# WL_PGA_ATT.net
KiCad netlist of a schematic drawn in Altium Designer
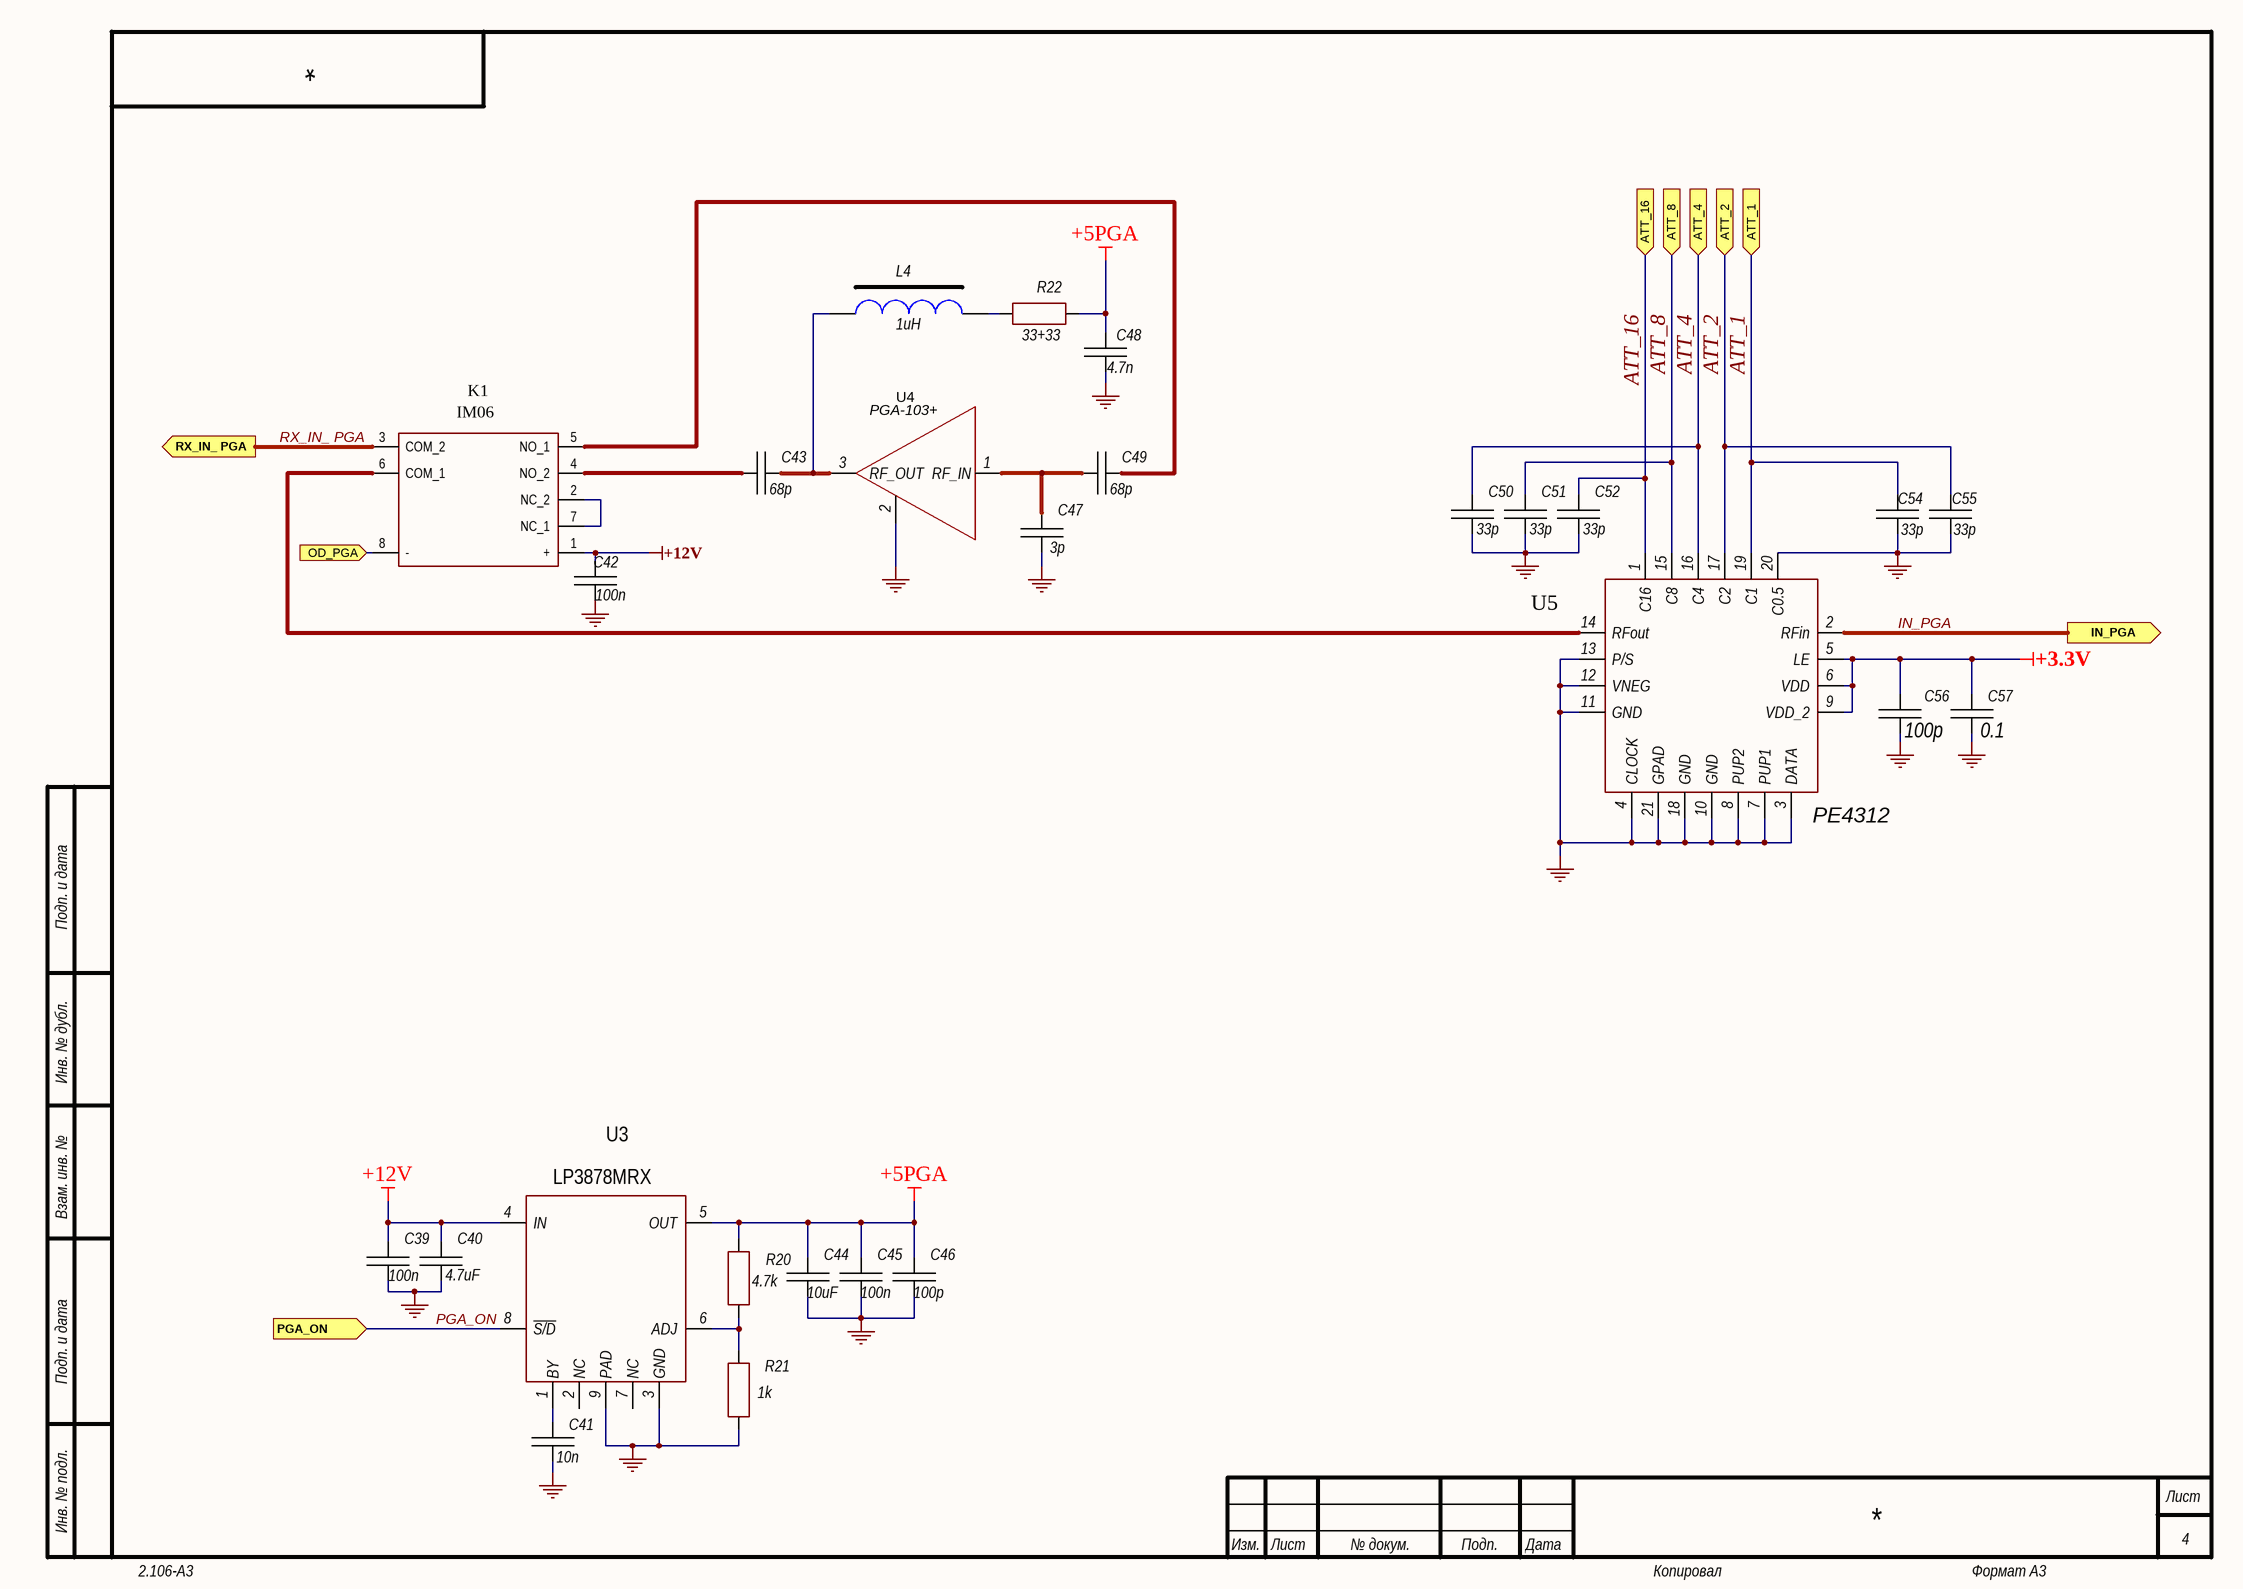
[diagram p0: WL_PGA_ATT.SchDoc]

(export (version "E")
  (design (tool "Eeschema 10.0.6"))
  (components
    (comp (ref "C39")
      (value "100n")
      (footprint "standard:CH0805C")
      (libsource (lib "Discrete") (part "Capacitor"))
    )
    (comp (ref "C40")
      (value "4.7uF")
      (footprint "standard:CH0805C")
      (libsource (lib "Discrete") (part "Capacitor"))
    )
    (comp (ref "C41")
      (value "10n")
      (footprint "standard:CH0805C")
      (libsource (lib "Discrete") (part "Capacitor"))
    )
    (comp (ref "C42")
      (value "100n")
      (footprint "standard:CH0805C")
      (libsource (lib "Discrete") (part "Capacitor"))
    )
    (comp (ref "C43")
      (value "68p")
      (footprint "standard:CH0805C")
      (libsource (lib "Discrete") (part "Capacitor"))
    )
    (comp (ref "C44")
      (value "10uF")
      (footprint "standard:CH0805C")
      (libsource (lib "Discrete") (part "Capacitor"))
    )
    (comp (ref "C45")
      (value "100n")
      (footprint "standard:CH0805C")
      (libsource (lib "Discrete") (part "Capacitor"))
    )
    (comp (ref "C46")
      (value "100p")
      (footprint "standard:CH0805C")
      (libsource (lib "Discrete") (part "Capacitor"))
    )
    (comp (ref "C47")
      (value "3p")
      (footprint "standard:CH0805C")
      (libsource (lib "Discrete") (part "Capacitor"))
    )
    (comp (ref "C48")
      (value "4.7n")
      (footprint "standard:CH0805C")
      (libsource (lib "Discrete") (part "Capacitor"))
    )
    (comp (ref "C49")
      (value "68p")
      (footprint "standard:CH0805C")
      (libsource (lib "Discrete") (part "Capacitor"))
    )
    (comp (ref "C50")
      (value "33p")
      (footprint "standard:CH0603C")
      (libsource (lib "Discrete") (part "Capacitor"))
    )
    (comp (ref "C51")
      (value "33p")
      (footprint "standard:CH0603C")
      (libsource (lib "Discrete") (part "Capacitor"))
    )
    (comp (ref "C52")
      (value "33p")
      (footprint "standard:CH0603C")
      (libsource (lib "Discrete") (part "Capacitor"))
    )
    (comp (ref "C54")
      (value "33p")
      (footprint "standard:CH0603C")
      (libsource (lib "Discrete") (part "Capacitor"))
    )
    (comp (ref "C55")
      (value "33p")
      (footprint "standard:CH0603C")
      (libsource (lib "Discrete") (part "Capacitor"))
    )
    (comp (ref "C56")
      (value "100p")
      (footprint "standard:CH0805C")
      (libsource (lib "Discrete") (part "Capacitor"))
    )
    (comp (ref "C57")
      (value "0.1")
      (footprint "standard:CH0805C")
      (libsource (lib "Discrete") (part "Capacitor"))
    )
    (comp (ref "K1") (value "IM06") (footprint "IM06") (libsource (lib "Relay") (part "IM06-V1")))
    (comp (ref "L4") (value "1uH") (footprint "L1210") (libsource (lib "Transformers") (part "TRANS")))
    (comp (ref "R20")
      (value "4.7k")
      (footprint "standard:CH0805R")
      (libsource (lib "Discrete") (part "Resistor"))
    )
    (comp (ref "R21")
      (value "1k")
      (footprint "standard:CH0805R")
      (libsource (lib "Discrete") (part "Resistor"))
    )
    (comp (ref "R22") (value "33+33") (footprint "WL_RFFC:CH1206R") (libsource (lib "") (part "Resistor_1")))
    (comp (ref "U3")
      (value "LP3878MRX")
      (footprint "8-SOIC (PAD)")
      (libsource (lib "Power Supplies") (part "LP3878"))
    )
    (comp (ref "U4") (value "PGA-103+") (footprint "SOT89_123") (libsource (lib "Digital") (part "PGA-103+")))
    (comp (ref "U5") (value "PE4312") (footprint "20-QFN (4x4)") (libsource (lib "Digital") (part "PE4302")))
  )
  (nets
    (net (code "1") (name "+3.3V") (class "Default")
      (node (ref "C56") (pin "1") (pinfunction "1_1") (pintype "passive"))
      (node (ref "C57") (pin "1") (pinfunction "1_1") (pintype "passive"))
      (node (ref "U5") (pin "5") (pinfunction "LE_5") (pintype "passive"))
      (node (ref "U5") (pin "6") (pinfunction "VDD_6") (pintype "passive"))
      (node (ref "U5") (pin "9") (pinfunction "VDD_2_9") (pintype "passive"))
    )
    (net (code "2") (name "+5PGA") (class "Default")
      (node (ref "C44") (pin "2") (pinfunction "2_2") (pintype "passive"))
      (node (ref "C45") (pin "2") (pinfunction "2_2") (pintype "passive"))
      (node (ref "C46") (pin "2") (pinfunction "2_2") (pintype "passive"))
      (node (ref "C48") (pin "2") (pinfunction "2_2") (pintype "passive"))
      (node (ref "R20") (pin "2") (pinfunction "2_2") (pintype "passive"))
      (node (ref "R22") (pin "2") (pinfunction "2_2") (pintype "passive"))
      (node (ref "U3") (pin "5") (pinfunction "OUT_5") (pintype "power_in"))
    )
    (net (code "3") (name "+12V") (class "Default")
      (node (ref "C39") (pin "2") (pinfunction "2_2") (pintype "passive"))
      (node (ref "C40") (pin "2") (pinfunction "2_2") (pintype "passive"))
      (node (ref "C42") (pin "2") (pinfunction "2_2") (pintype "passive"))
      (node (ref "K1") (pin "1") (pinfunction "+_1") (pintype "passive"))
      (node (ref "U3") (pin "4") (pinfunction "IN_4") (pintype "power_in"))
    )
    (net (code "4") (name "/ATT_1") (class "Default")
      (node (ref "C54") (pin "2") (pinfunction "2_2") (pintype "passive"))
      (node (ref "U5") (pin "19") (pinfunction "C1_19") (pintype "passive"))
    )
    (net (code "5") (name "/ATT_2") (class "Default")
      (node (ref "C55") (pin "2") (pinfunction "2_2") (pintype "passive"))
      (node (ref "U5") (pin "17") (pinfunction "C2_17") (pintype "passive"))
    )
    (net (code "6") (name "/ATT_4") (class "Default")
      (node (ref "C50") (pin "2") (pinfunction "2_2") (pintype "passive"))
      (node (ref "U5") (pin "16") (pinfunction "C4_16") (pintype "passive"))
    )
    (net (code "7") (name "/ATT_8") (class "Default")
      (node (ref "C51") (pin "2") (pinfunction "2_2") (pintype "passive"))
      (node (ref "U5") (pin "15") (pinfunction "C8_15") (pintype "passive"))
    )
    (net (code "8") (name "/ATT_16") (class "Default")
      (node (ref "C52") (pin "2") (pinfunction "2_2") (pintype "passive"))
      (node (ref "U5") (pin "1") (pinfunction "C16_1") (pintype "passive"))
    )
    (net (code "9") (name "/IN_PGA") (class "Default")
      (node (ref "U5") (pin "2") (pinfunction "RFin_2") (pintype "passive"))
    )
    (net (code "10") (name "/OD_PGA") (class "Default")
      (node (ref "K1") (pin "8") (pinfunction "-_8") (pintype "passive"))
    )
    (net (code "11") (name "/PGA_ON") (class "Default")
      (node (ref "U3") (pin "8") (pinfunction "~{S/D}_8") (pintype "power_in"))
    )
    (net (code "12") (name "/RX_IN_ PGA") (class "Default")
      (node (ref "K1") (pin "3") (pinfunction "COM_2_3") (pintype "passive"))
    )
    (net (code "13") (name "GND") (class "Default")
      (node (ref "C39") (pin "1") (pinfunction "1_1") (pintype "passive"))
      (node (ref "C40") (pin "1") (pinfunction "1_1") (pintype "passive"))
      (node (ref "C41") (pin "1") (pinfunction "1_1") (pintype "passive"))
      (node (ref "C42") (pin "1") (pinfunction "1_1") (pintype "passive"))
      (node (ref "C44") (pin "1") (pinfunction "1_1") (pintype "passive"))
      (node (ref "C45") (pin "1") (pinfunction "1_1") (pintype "passive"))
      (node (ref "C46") (pin "1") (pinfunction "1_1") (pintype "passive"))
      (node (ref "C47") (pin "1") (pinfunction "1_1") (pintype "passive"))
      (node (ref "C48") (pin "1") (pinfunction "1_1") (pintype "passive"))
      (node (ref "C50") (pin "1") (pinfunction "1_1") (pintype "passive"))
      (node (ref "C51") (pin "1") (pinfunction "1_1") (pintype "passive"))
      (node (ref "C52") (pin "1") (pinfunction "1_1") (pintype "passive"))
      (node (ref "C54") (pin "1") (pinfunction "1_1") (pintype "passive"))
      (node (ref "C55") (pin "1") (pinfunction "1_1") (pintype "passive"))
      (node (ref "C56") (pin "2") (pinfunction "2_2") (pintype "passive"))
      (node (ref "C57") (pin "2") (pinfunction "2_2") (pintype "passive"))
      (node (ref "R21") (pin "1") (pinfunction "1_1") (pintype "passive"))
      (node (ref "U3") (pin "3") (pinfunction "GND_3") (pintype "passive"))
      (node (ref "U3") (pin "9") (pinfunction "PAD_9") (pintype "passive"))
      (node (ref "U4") (pin "2") (pinfunction "GND_2") (pintype "passive"))
      (node (ref "U5") (pin "10") (pinfunction "GND_10") (pintype "passive"))
      (node (ref "U5") (pin "11") (pinfunction "GND_11") (pintype "passive"))
      (node (ref "U5") (pin "12") (pinfunction "VNEG_12") (pintype "passive"))
      (node (ref "U5") (pin "13") (pinfunction "P/S_13") (pintype "passive"))
      (node (ref "U5") (pin "18") (pinfunction "GND_18") (pintype "passive"))
      (node (ref "U5") (pin "20") (pinfunction "C0.5_20") (pintype "passive"))
      (node (ref "U5") (pin "21") (pinfunction "GPAD_21") (pintype "passive"))
      (node (ref "U5") (pin "3") (pinfunction "DATA_3") (pintype "passive"))
      (node (ref "U5") (pin "4") (pinfunction "CLOCK_4") (pintype "passive"))
      (node (ref "U5") (pin "7") (pinfunction "PUP1_7") (pintype "passive"))
      (node (ref "U5") (pin "8") (pinfunction "PUP2_8") (pintype "passive"))
    )
    (net (code "14") (name "Net-(K1-COM_1)") (class "Default")
      (node (ref "K1") (pin "6") (pinfunction "COM_1_6") (pintype "passive"))
      (node (ref "U5") (pin "14") (pinfunction "RFout_14") (pintype "passive"))
    )
    (net (code "15") (name "Net-(K1-NC_1)") (class "Default")
      (node (ref "K1") (pin "2") (pinfunction "NC_2_2") (pintype "passive"))
      (node (ref "K1") (pin "7") (pinfunction "NC_1_7") (pintype "passive"))
    )
    (net (code "16") (name "Net-(K1-NO_1)") (class "Default")
      (node (ref "C49") (pin "2") (pinfunction "2_2") (pintype "passive"))
      (node (ref "K1") (pin "5") (pinfunction "NO_1_5") (pintype "passive"))
    )
    (net (code "17") (name "Net-(K1-NO_2)") (class "Default")
      (node (ref "C43") (pin "1") (pinfunction "1_1") (pintype "passive"))
      (node (ref "K1") (pin "4") (pinfunction "NO_2_4") (pintype "passive"))
    )
    (net (code "18") (name "Net-(L4-Pad1)") (class "Default")
      (node (ref "L4") (pin "1") (pinfunction "1_1") (pintype "power_in"))
      (node (ref "R22") (pin "1") (pinfunction "1_1") (pintype "passive"))
    )
    (net (code "19") (name "Net-(U3-ADJ)") (class "Default")
      (node (ref "R20") (pin "1") (pinfunction "1_1") (pintype "passive"))
      (node (ref "R21") (pin "2") (pinfunction "2_2") (pintype "passive"))
      (node (ref "U3") (pin "6") (pinfunction "ADJ_6") (pintype "passive"))
    )
    (net (code "20") (name "Net-(U3-BY)") (class "Default")
      (node (ref "C41") (pin "2") (pinfunction "2_2") (pintype "passive"))
      (node (ref "U3") (pin "1") (pinfunction "BY_1") (pintype "passive"))
    )
    (net (code "21") (name "Net-(U4-RF_IN)") (class "Default")
      (node (ref "C47") (pin "2") (pinfunction "2_2") (pintype "passive"))
      (node (ref "C49") (pin "1") (pinfunction "1_1") (pintype "passive"))
      (node (ref "U4") (pin "1") (pinfunction "RF_IN_1") (pintype "passive"))
    )
    (net (code "22") (name "Net-(U4-RF_OUT)") (class "Default")
      (node (ref "C43") (pin "2") (pinfunction "2_2") (pintype "passive"))
      (node (ref "L4") (pin "2") (pinfunction "2_2") (pintype "power_in"))
      (node (ref "U4") (pin "3") (pinfunction "RF_OUT_3") (pintype "passive"))
    )
    (net (code "23") (name "unconnected-(U3-NC-Pad2)") (class "Default")
      (node (ref "U3") (pin "2") (pinfunction "NC_2") (pintype "passive"))
    )
    (net (code "24") (name "unconnected-(U3-NC-Pad7)") (class "Default")
      (node (ref "U3") (pin "7") (pinfunction "NC_7") (pintype "passive"))
    )
  )
)
